# PS_cubesat_baterias.net
KiCad netlist of a schematic drawn in EAGLE
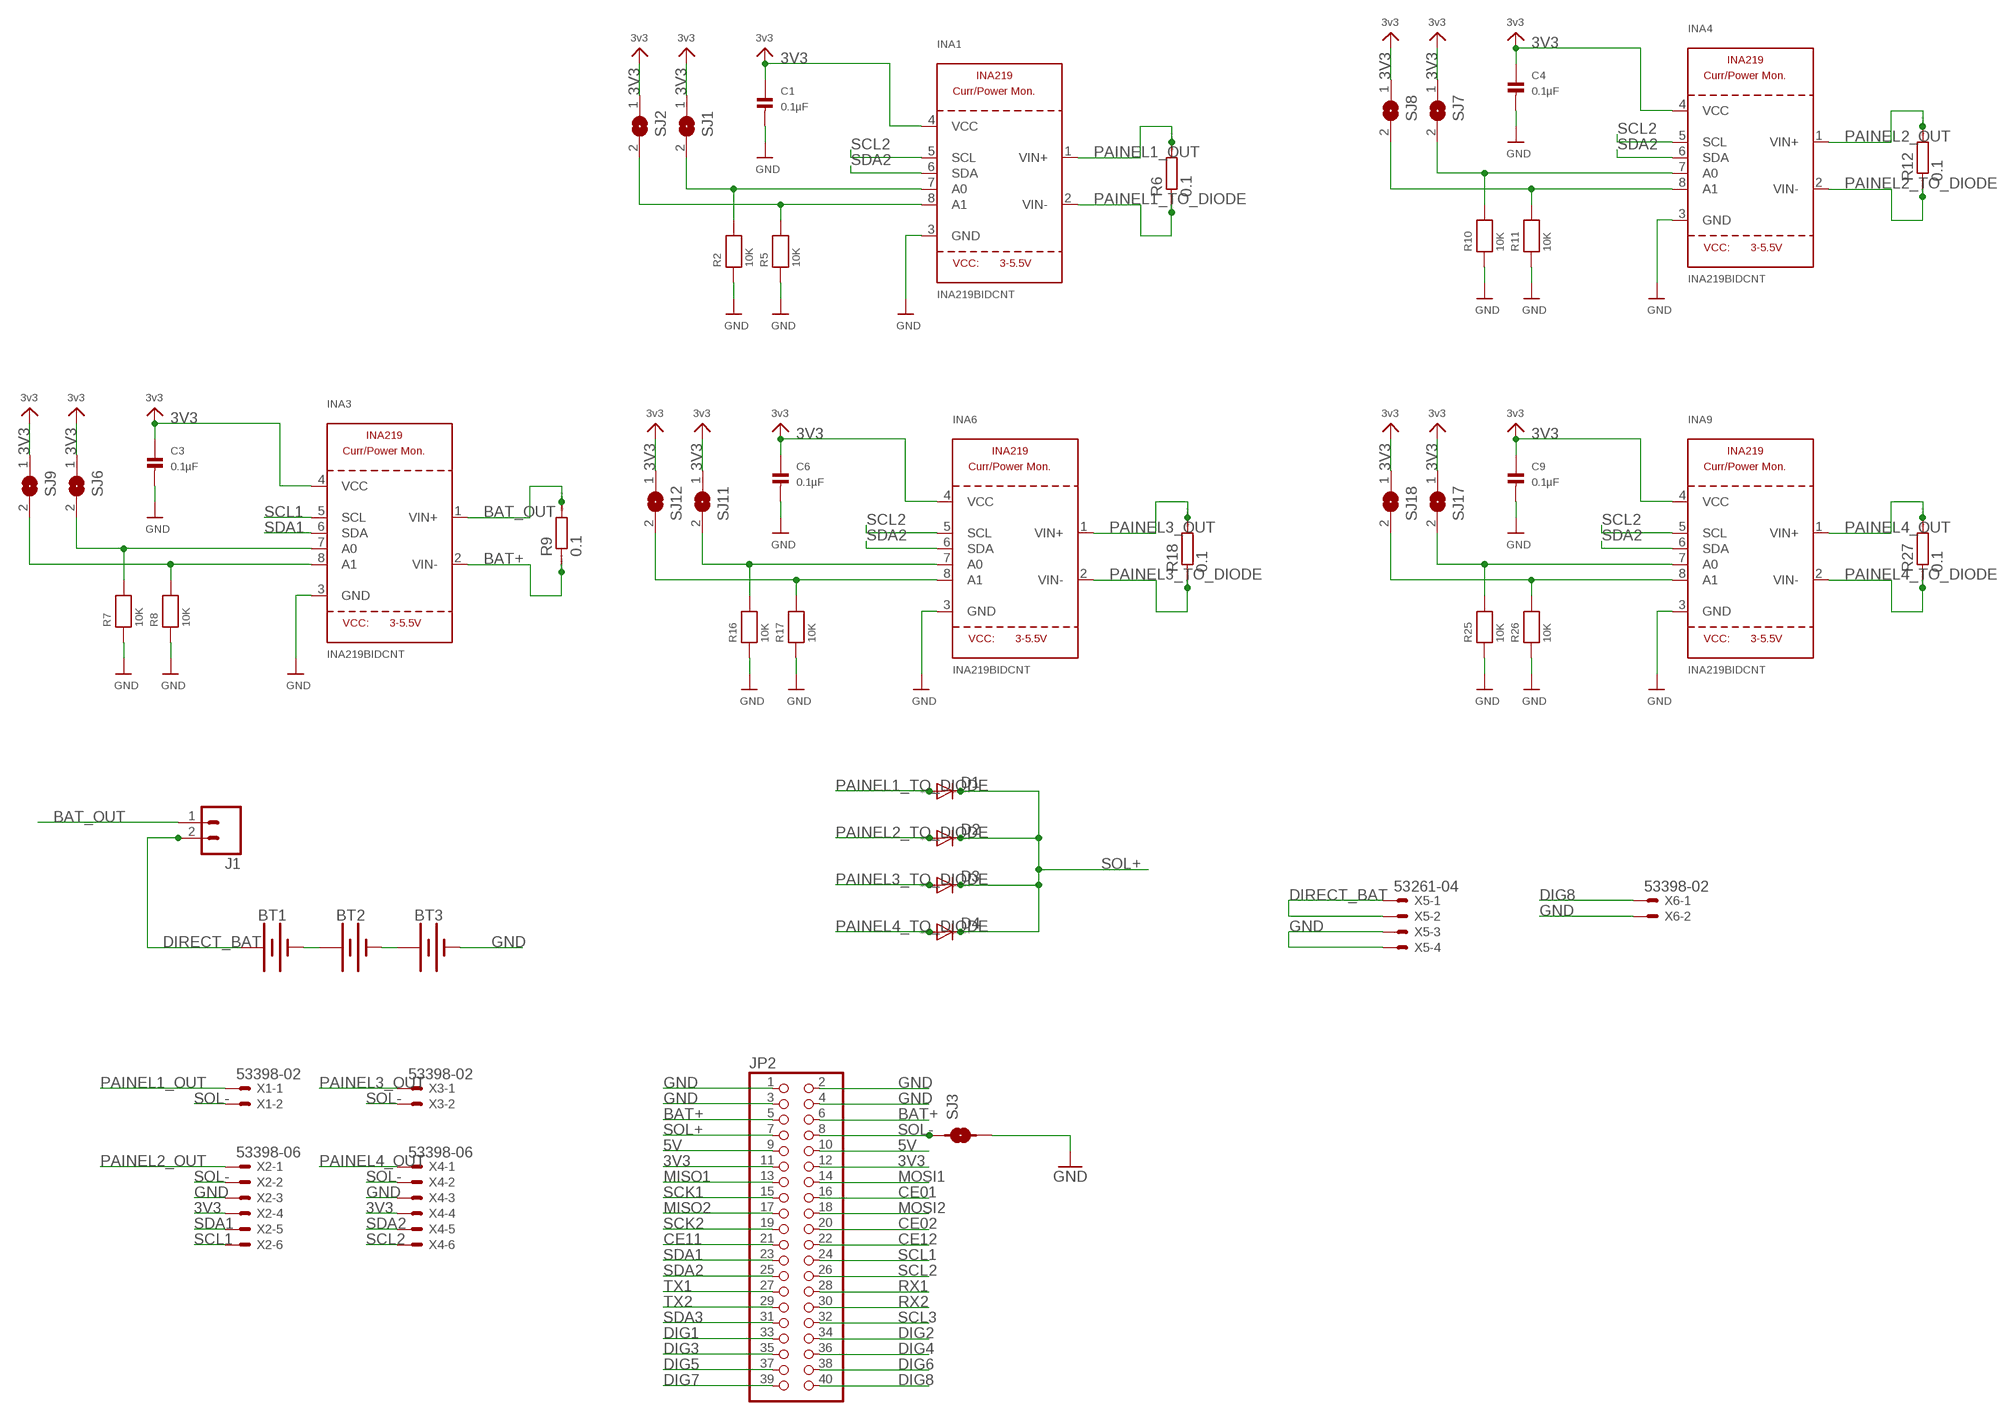
[diagram p0: schematic, sheet 1]

(export (version "E")
  (design (tool "Eeschema 10.0.6"))
  (components
    (comp (ref "BT1")
      (value "BATTERY-18650")
      (footprint "eagle-import:BATTERY_18650-HOLDER")
      (libsource (lib "eagle-import") (part "BATTERY-18650"))
    )
    (comp (ref "BT2")
      (value "BATTERY-18650")
      (footprint "eagle-import:BATTERY_18650-HOLDER")
      (libsource (lib "eagle-import") (part "BATTERY-18650"))
    )
    (comp (ref "BT3")
      (value "BATTERY-18650")
      (footprint "eagle-import:BATTERY_18650-HOLDER")
      (libsource (lib "eagle-import") (part "BATTERY-18650"))
    )
    (comp (ref "C1")
      (value "0.1µF")
      (footprint "eagle-import:1206")
      (libsource (lib "eagle-import") (part "CAP_CERAMIC1206"))
    )
    (comp (ref "C3")
      (value "0.1µF")
      (footprint "eagle-import:1206")
      (libsource (lib "eagle-import") (part "CAP_CERAMIC1206"))
    )
    (comp (ref "C4")
      (value "0.1µF")
      (footprint "eagle-import:1206")
      (libsource (lib "eagle-import") (part "CAP_CERAMIC1206"))
    )
    (comp (ref "C6")
      (value "0.1µF")
      (footprint "eagle-import:1206")
      (libsource (lib "eagle-import") (part "CAP_CERAMIC1206"))
    )
    (comp (ref "C9")
      (value "0.1µF")
      (footprint "eagle-import:1206")
      (libsource (lib "eagle-import") (part "CAP_CERAMIC1206"))
    )
    (comp (ref "D1")
      (value "DIODE-DO-214AC")
      (footprint "eagle-import:DO-214AC")
      (libsource (lib "eagle-import") (part "DIODE-DO-214AC"))
    )
    (comp (ref "D2")
      (value "DIODE-DO-214AC")
      (footprint "eagle-import:DO-214AC")
      (libsource (lib "eagle-import") (part "DIODE-DO-214AC"))
    )
    (comp (ref "D3")
      (value "DIODE-DO-214AC")
      (footprint "eagle-import:DO-214AC")
      (libsource (lib "eagle-import") (part "DIODE-DO-214AC"))
    )
    (comp (ref "D4")
      (value "DIODE-DO-214AC")
      (footprint "eagle-import:DO-214AC")
      (libsource (lib "eagle-import") (part "DIODE-DO-214AC"))
    )
    (comp (ref "INA1")
      (value "INA219BIDCNT")
      (footprint "eagle-import:SOT23-8")
      (libsource (lib "eagle-import") (part "INA219"))
    )
    (comp (ref "INA3")
      (value "INA219BIDCNT")
      (footprint "eagle-import:SOT23-8")
      (libsource (lib "eagle-import") (part "INA219"))
    )
    (comp (ref "INA4")
      (value "INA219BIDCNT")
      (footprint "eagle-import:SOT23-8")
      (libsource (lib "eagle-import") (part "INA219"))
    )
    (comp (ref "INA6")
      (value "INA219BIDCNT")
      (footprint "eagle-import:SOT23-8")
      (libsource (lib "eagle-import") (part "INA219"))
    )
    (comp (ref "INA9")
      (value "INA219BIDCNT")
      (footprint "eagle-import:SOT23-8")
      (libsource (lib "eagle-import") (part "INA219"))
    )
    (comp (ref "J1")
      (value "M02JST-PTH-VERT")
      (footprint "eagle-import:JST-2-PTH-VERT")
      (libsource (lib "eagle-import") (part "M02JST-PTH-VERT"))
    )
    (comp (ref "JP2")
      (value "PINHD-2X20")
      (footprint "eagle-import:2X20")
      (libsource (lib "eagle-import") (part "PINHD-2X20"))
    )
    (comp (ref "R2")
      (value "10K")
      (footprint "eagle-import:1206")
      (libsource (lib "eagle-import") (part "RESISTOR1206"))
    )
    (comp (ref "R5")
      (value "10K")
      (footprint "eagle-import:1206")
      (libsource (lib "eagle-import") (part "RESISTOR1206"))
    )
    (comp (ref "R6")
      (value "0.1")
      (footprint "eagle-import:R2512")
      (libsource (lib "eagle-import") (part "RR2512"))
    )
    (comp (ref "R7")
      (value "10K")
      (footprint "eagle-import:1206")
      (libsource (lib "eagle-import") (part "RESISTOR1206"))
    )
    (comp (ref "R8")
      (value "10K")
      (footprint "eagle-import:1206")
      (libsource (lib "eagle-import") (part "RESISTOR1206"))
    )
    (comp (ref "R9")
      (value "0.1")
      (footprint "eagle-import:R2512")
      (libsource (lib "eagle-import") (part "RR2512"))
    )
    (comp (ref "R10")
      (value "10K")
      (footprint "eagle-import:1206")
      (libsource (lib "eagle-import") (part "RESISTOR1206"))
    )
    (comp (ref "R11")
      (value "10K")
      (footprint "eagle-import:1206")
      (libsource (lib "eagle-import") (part "RESISTOR1206"))
    )
    (comp (ref "R12")
      (value "0.1")
      (footprint "eagle-import:R2512")
      (libsource (lib "eagle-import") (part "RR2512"))
    )
    (comp (ref "R16")
      (value "10K")
      (footprint "eagle-import:1206")
      (libsource (lib "eagle-import") (part "RESISTOR1206"))
    )
    (comp (ref "R17")
      (value "10K")
      (footprint "eagle-import:1206")
      (libsource (lib "eagle-import") (part "RESISTOR1206"))
    )
    (comp (ref "R18")
      (value "0.1")
      (footprint "eagle-import:R2512")
      (libsource (lib "eagle-import") (part "RR2512"))
    )
    (comp (ref "R25")
      (value "10K")
      (footprint "eagle-import:1206")
      (libsource (lib "eagle-import") (part "RESISTOR1206"))
    )
    (comp (ref "R26")
      (value "10K")
      (footprint "eagle-import:1206")
      (libsource (lib "eagle-import") (part "RESISTOR1206"))
    )
    (comp (ref "R27")
      (value "0.1")
      (footprint "eagle-import:R2512")
      (libsource (lib "eagle-import") (part "RR2512"))
    )
    (comp (ref "SJ1")
      (value "SOLDERJUMPERREFLOW_NOPASTE")
      (footprint "eagle-import:SOLDERJUMPER_REFLOW_NOPASTE")
      (libsource (lib "eagle-import") (part "SOLDERJUMPERREFLOW_NOPASTE"))
    )
    (comp (ref "SJ2")
      (value "SOLDERJUMPERREFLOW_NOPASTE")
      (footprint "eagle-import:SOLDERJUMPER_REFLOW_NOPASTE")
      (libsource (lib "eagle-import") (part "SOLDERJUMPERREFLOW_NOPASTE"))
    )
    (comp (ref "SJ3")
      (value "SMD-JUMPER-2")
      (footprint "eagle-import:SMD-JUMPER-2")
      (libsource (lib "eagle-import") (part "SMD-JUMPER-2"))
    )
    (comp (ref "SJ6")
      (value "SOLDERJUMPERREFLOW_NOPASTE")
      (footprint "eagle-import:SOLDERJUMPER_REFLOW_NOPASTE")
      (libsource (lib "eagle-import") (part "SOLDERJUMPERREFLOW_NOPASTE"))
    )
    (comp (ref "SJ7")
      (value "SOLDERJUMPERREFLOW_NOPASTE")
      (footprint "eagle-import:SOLDERJUMPER_REFLOW_NOPASTE")
      (libsource (lib "eagle-import") (part "SOLDERJUMPERREFLOW_NOPASTE"))
    )
    (comp (ref "SJ8")
      (value "SOLDERJUMPERREFLOW_NOPASTE")
      (footprint "eagle-import:SOLDERJUMPER_REFLOW_NOPASTE")
      (libsource (lib "eagle-import") (part "SOLDERJUMPERREFLOW_NOPASTE"))
    )
    (comp (ref "SJ9")
      (value "SOLDERJUMPERREFLOW_NOPASTE")
      (footprint "eagle-import:SOLDERJUMPER_REFLOW_NOPASTE")
      (libsource (lib "eagle-import") (part "SOLDERJUMPERREFLOW_NOPASTE"))
    )
    (comp (ref "SJ11")
      (value "SOLDERJUMPERREFLOW_NOPASTE")
      (footprint "eagle-import:SOLDERJUMPER_REFLOW_NOPASTE")
      (libsource (lib "eagle-import") (part "SOLDERJUMPERREFLOW_NOPASTE"))
    )
    (comp (ref "SJ12")
      (value "SOLDERJUMPERREFLOW_NOPASTE")
      (footprint "eagle-import:SOLDERJUMPER_REFLOW_NOPASTE")
      (libsource (lib "eagle-import") (part "SOLDERJUMPERREFLOW_NOPASTE"))
    )
    (comp (ref "SJ17")
      (value "SOLDERJUMPERREFLOW_NOPASTE")
      (footprint "eagle-import:SOLDERJUMPER_REFLOW_NOPASTE")
      (libsource (lib "eagle-import") (part "SOLDERJUMPERREFLOW_NOPASTE"))
    )
    (comp (ref "SJ18")
      (value "SOLDERJUMPERREFLOW_NOPASTE")
      (footprint "eagle-import:SOLDERJUMPER_REFLOW_NOPASTE")
      (libsource (lib "eagle-import") (part "SOLDERJUMPERREFLOW_NOPASTE"))
    )
    (comp (ref "X1")
      (value "53398-02")
      (footprint "eagle-import:53398-02")
      (fields (field (name "MF") "MOLEX"))
      (libsource (lib "eagle-import") (part "53?-02398"))
    )
    (comp (ref "X2")
      (value "53398-06")
      (footprint "eagle-import:53398-06")
      (fields (field (name "MF") "MOLEX"))
      (libsource (lib "eagle-import") (part "53?-06398"))
    )
    (comp (ref "X3")
      (value "53398-02")
      (footprint "eagle-import:53398-02")
      (fields (field (name "MF") "MOLEX"))
      (libsource (lib "eagle-import") (part "53?-02398"))
    )
    (comp (ref "X4")
      (value "53398-06")
      (footprint "eagle-import:53398-06")
      (fields (field (name "MF") "MOLEX"))
      (libsource (lib "eagle-import") (part "53?-06398"))
    )
    (comp (ref "X5")
      (value "53261-04")
      (footprint "eagle-import:53261-04")
      (fields (field (name "MF") "MOLEX"))
      (libsource (lib "eagle-import") (part "53?-04261"))
    )
    (comp (ref "X6")
      (value "53398-02")
      (footprint "eagle-import:53398-02")
      (fields (field (name "MF") "MOLEX"))
      (libsource (lib "eagle-import") (part "53?-02398"))
    )
  )
  (nets
    (net (code "1") (name "/5V") (class "Default")
      (node (ref "JP2") (pin "10") (pinfunction "10_10") (pintype "passive"))
      (node (ref "JP2") (pin "9") (pinfunction "9_9") (pintype "passive"))
    )
    (net (code "2") (name "/BAT+") (class "Default")
      (node (ref "INA3") (pin "2") (pinfunction "VIN-_2") (pintype "bidirectional"))
      (node (ref "JP2") (pin "5") (pinfunction "5_5") (pintype "passive"))
      (node (ref "JP2") (pin "6") (pinfunction "6_6") (pintype "passive"))
      (node (ref "R9") (pin "1") (pinfunction "1_1") (pintype "passive"))
    )
    (net (code "3") (name "/BAT_OUT") (class "Default")
      (node (ref "INA3") (pin "1") (pinfunction "VIN+_1") (pintype "bidirectional"))
      (node (ref "J1") (pin "1") (pinfunction "1_1") (pintype "passive"))
      (node (ref "R9") (pin "2") (pinfunction "2_2") (pintype "passive"))
    )
    (net (code "4") (name "/CE01") (class "Default")
      (node (ref "JP2") (pin "16") (pinfunction "16_16") (pintype "passive"))
    )
    (net (code "5") (name "/CE02") (class "Default")
      (node (ref "JP2") (pin "20") (pinfunction "20_20") (pintype "passive"))
    )
    (net (code "6") (name "/CE11") (class "Default")
      (node (ref "JP2") (pin "21") (pinfunction "21_21") (pintype "passive"))
    )
    (net (code "7") (name "/CE12") (class "Default")
      (node (ref "JP2") (pin "22") (pinfunction "22_22") (pintype "passive"))
    )
    (net (code "8") (name "/DIG1") (class "Default")
      (node (ref "JP2") (pin "33") (pinfunction "33_33") (pintype "passive"))
    )
    (net (code "9") (name "/DIG2") (class "Default")
      (node (ref "JP2") (pin "34") (pinfunction "34_34") (pintype "passive"))
    )
    (net (code "10") (name "/DIG3") (class "Default")
      (node (ref "JP2") (pin "35") (pinfunction "35_35") (pintype "passive"))
    )
    (net (code "11") (name "/DIG4") (class "Default")
      (node (ref "JP2") (pin "36") (pinfunction "36_36") (pintype "passive"))
    )
    (net (code "12") (name "/DIG5") (class "Default")
      (node (ref "JP2") (pin "37") (pinfunction "37_37") (pintype "passive"))
    )
    (net (code "13") (name "/DIG6") (class "Default")
      (node (ref "JP2") (pin "38") (pinfunction "38_38") (pintype "passive"))
    )
    (net (code "14") (name "/DIG7") (class "Default")
      (node (ref "JP2") (pin "39") (pinfunction "39_39") (pintype "passive"))
    )
    (net (code "15") (name "/DIG8") (class "Default")
      (node (ref "JP2") (pin "40") (pinfunction "40_40") (pintype "passive"))
      (node (ref "X6") (pin "1") (pinfunction "S_1") (pintype "passive"))
    )
    (net (code "16") (name "/DIRECT_BAT") (class "Default")
      (node (ref "BT1") (pin "PWR@1") (pinfunction "+_PWR@1") (pintype "power_in"))
      (node (ref "J1") (pin "2") (pinfunction "2_2") (pintype "passive"))
      (node (ref "X5") (pin "1") (pinfunction "S_1") (pintype "passive"))
      (node (ref "X5") (pin "2") (pinfunction "S_2") (pintype "passive"))
    )
    (net (code "17") (name "/MISO1") (class "Default")
      (node (ref "JP2") (pin "13") (pinfunction "13_13") (pintype "passive"))
    )
    (net (code "18") (name "/MISO2") (class "Default")
      (node (ref "JP2") (pin "17") (pinfunction "17_17") (pintype "passive"))
    )
    (net (code "19") (name "/MOSI1") (class "Default")
      (node (ref "JP2") (pin "14") (pinfunction "14_14") (pintype "passive"))
    )
    (net (code "20") (name "/MOSI2") (class "Default")
      (node (ref "JP2") (pin "18") (pinfunction "18_18") (pintype "passive"))
    )
    (net (code "21") (name "/PAINEL1_OUT") (class "Default")
      (node (ref "INA1") (pin "1") (pinfunction "VIN+_1") (pintype "bidirectional"))
      (node (ref "R6") (pin "2") (pinfunction "2_2") (pintype "passive"))
      (node (ref "X1") (pin "1") (pinfunction "S_1") (pintype "passive"))
    )
    (net (code "22") (name "/PAINEL1_TO_DIODE") (class "Default")
      (node (ref "D1") (pin "A") (pinfunction "A_A") (pintype "passive"))
      (node (ref "INA1") (pin "2") (pinfunction "VIN-_2") (pintype "bidirectional"))
      (node (ref "R6") (pin "1") (pinfunction "1_1") (pintype "passive"))
    )
    (net (code "23") (name "/PAINEL2_OUT") (class "Default")
      (node (ref "INA4") (pin "1") (pinfunction "VIN+_1") (pintype "bidirectional"))
      (node (ref "R12") (pin "2") (pinfunction "2_2") (pintype "passive"))
      (node (ref "X2") (pin "1") (pinfunction "S_1") (pintype "passive"))
    )
    (net (code "24") (name "/PAINEL2_TO_DIODE") (class "Default")
      (node (ref "D2") (pin "A") (pinfunction "A_A") (pintype "passive"))
      (node (ref "INA4") (pin "2") (pinfunction "VIN-_2") (pintype "bidirectional"))
      (node (ref "R12") (pin "1") (pinfunction "1_1") (pintype "passive"))
    )
    (net (code "25") (name "/PAINEL3_OUT") (class "Default")
      (node (ref "INA6") (pin "1") (pinfunction "VIN+_1") (pintype "bidirectional"))
      (node (ref "R18") (pin "2") (pinfunction "2_2") (pintype "passive"))
      (node (ref "X3") (pin "1") (pinfunction "S_1") (pintype "passive"))
    )
    (net (code "26") (name "/PAINEL3_TO_DIODE") (class "Default")
      (node (ref "D3") (pin "A") (pinfunction "A_A") (pintype "passive"))
      (node (ref "INA6") (pin "2") (pinfunction "VIN-_2") (pintype "bidirectional"))
      (node (ref "R18") (pin "1") (pinfunction "1_1") (pintype "passive"))
    )
    (net (code "27") (name "/PAINEL4_OUT") (class "Default")
      (node (ref "INA9") (pin "1") (pinfunction "VIN+_1") (pintype "bidirectional"))
      (node (ref "R27") (pin "2") (pinfunction "2_2") (pintype "passive"))
      (node (ref "X4") (pin "1") (pinfunction "S_1") (pintype "passive"))
    )
    (net (code "28") (name "/PAINEL4_TO_DIODE") (class "Default")
      (node (ref "D4") (pin "A") (pinfunction "A_A") (pintype "passive"))
      (node (ref "INA9") (pin "2") (pinfunction "VIN-_2") (pintype "bidirectional"))
      (node (ref "R27") (pin "1") (pinfunction "1_1") (pintype "passive"))
    )
    (net (code "29") (name "/RX1") (class "Default")
      (node (ref "JP2") (pin "28") (pinfunction "28_28") (pintype "passive"))
    )
    (net (code "30") (name "/RX2") (class "Default")
      (node (ref "JP2") (pin "30") (pinfunction "30_30") (pintype "passive"))
    )
    (net (code "31") (name "/SCK1") (class "Default")
      (node (ref "JP2") (pin "15") (pinfunction "15_15") (pintype "passive"))
    )
    (net (code "32") (name "/SCK2") (class "Default")
      (node (ref "JP2") (pin "19") (pinfunction "19_19") (pintype "passive"))
    )
    (net (code "33") (name "/SCL1") (class "Default")
      (node (ref "INA3") (pin "5") (pinfunction "SCL_5") (pintype "bidirectional"))
      (node (ref "JP2") (pin "24") (pinfunction "24_24") (pintype "passive"))
      (node (ref "X2") (pin "6") (pinfunction "S_6") (pintype "passive"))
    )
    (net (code "34") (name "/SCL2") (class "Default")
      (node (ref "INA1") (pin "5") (pinfunction "SCL_5") (pintype "bidirectional"))
      (node (ref "INA4") (pin "5") (pinfunction "SCL_5") (pintype "bidirectional"))
      (node (ref "INA6") (pin "5") (pinfunction "SCL_5") (pintype "bidirectional"))
      (node (ref "INA9") (pin "5") (pinfunction "SCL_5") (pintype "bidirectional"))
      (node (ref "JP2") (pin "26") (pinfunction "26_26") (pintype "passive"))
      (node (ref "X4") (pin "6") (pinfunction "S_6") (pintype "passive"))
    )
    (net (code "35") (name "/SCL3") (class "Default")
      (node (ref "JP2") (pin "32") (pinfunction "32_32") (pintype "passive"))
    )
    (net (code "36") (name "/SDA1") (class "Default")
      (node (ref "INA3") (pin "6") (pinfunction "SDA_6") (pintype "bidirectional"))
      (node (ref "JP2") (pin "23") (pinfunction "23_23") (pintype "passive"))
      (node (ref "X2") (pin "5") (pinfunction "S_5") (pintype "passive"))
    )
    (net (code "37") (name "/SDA2") (class "Default")
      (node (ref "INA1") (pin "6") (pinfunction "SDA_6") (pintype "bidirectional"))
      (node (ref "INA4") (pin "6") (pinfunction "SDA_6") (pintype "bidirectional"))
      (node (ref "INA6") (pin "6") (pinfunction "SDA_6") (pintype "bidirectional"))
      (node (ref "INA9") (pin "6") (pinfunction "SDA_6") (pintype "bidirectional"))
      (node (ref "JP2") (pin "25") (pinfunction "25_25") (pintype "passive"))
      (node (ref "X4") (pin "5") (pinfunction "S_5") (pintype "passive"))
    )
    (net (code "38") (name "/SDA3") (class "Default")
      (node (ref "JP2") (pin "31") (pinfunction "31_31") (pintype "passive"))
    )
    (net (code "39") (name "/SOL+") (class "Default")
      (node (ref "D1") (pin "C") (pinfunction "C_C") (pintype "passive"))
      (node (ref "D2") (pin "C") (pinfunction "C_C") (pintype "passive"))
      (node (ref "D3") (pin "C") (pinfunction "C_C") (pintype "passive"))
      (node (ref "D4") (pin "C") (pinfunction "C_C") (pintype "passive"))
      (node (ref "JP2") (pin "7") (pinfunction "7_7") (pintype "passive"))
    )
    (net (code "40") (name "/SOL-") (class "Default")
      (node (ref "JP2") (pin "8") (pinfunction "8_8") (pintype "passive"))
      (node (ref "SJ3") (pin "1") (pinfunction "1_1") (pintype "passive"))
      (node (ref "X1") (pin "2") (pinfunction "S_2") (pintype "passive"))
      (node (ref "X2") (pin "2") (pinfunction "S_2") (pintype "passive"))
      (node (ref "X3") (pin "2") (pinfunction "S_2") (pintype "passive"))
      (node (ref "X4") (pin "2") (pinfunction "S_2") (pintype "passive"))
    )
    (net (code "41") (name "/TX1") (class "Default")
      (node (ref "JP2") (pin "27") (pinfunction "27_27") (pintype "passive"))
    )
    (net (code "42") (name "/TX2") (class "Default")
      (node (ref "JP2") (pin "29") (pinfunction "29_29") (pintype "passive"))
    )
    (net (code "43") (name "3v3") (class "Default")
      (node (ref "C1") (pin "1") (pinfunction "P$1_1") (pintype "passive"))
      (node (ref "C3") (pin "1") (pinfunction "P$1_1") (pintype "passive"))
      (node (ref "C4") (pin "1") (pinfunction "P$1_1") (pintype "passive"))
      (node (ref "C6") (pin "1") (pinfunction "P$1_1") (pintype "passive"))
      (node (ref "C9") (pin "1") (pinfunction "P$1_1") (pintype "passive"))
      (node (ref "INA1") (pin "4") (pinfunction "VCC_4") (pintype "bidirectional"))
      (node (ref "INA3") (pin "4") (pinfunction "VCC_4") (pintype "bidirectional"))
      (node (ref "INA4") (pin "4") (pinfunction "VCC_4") (pintype "bidirectional"))
      (node (ref "INA6") (pin "4") (pinfunction "VCC_4") (pintype "bidirectional"))
      (node (ref "INA9") (pin "4") (pinfunction "VCC_4") (pintype "bidirectional"))
      (node (ref "JP2") (pin "11") (pinfunction "11_11") (pintype "passive"))
      (node (ref "JP2") (pin "12") (pinfunction "12_12") (pintype "passive"))
      (node (ref "SJ1") (pin "1") (pinfunction "1_1") (pintype "passive"))
      (node (ref "SJ11") (pin "1") (pinfunction "1_1") (pintype "passive"))
      (node (ref "SJ12") (pin "1") (pinfunction "1_1") (pintype "passive"))
      (node (ref "SJ17") (pin "1") (pinfunction "1_1") (pintype "passive"))
      (node (ref "SJ18") (pin "1") (pinfunction "1_1") (pintype "passive"))
      (node (ref "SJ2") (pin "1") (pinfunction "1_1") (pintype "passive"))
      (node (ref "SJ6") (pin "1") (pinfunction "1_1") (pintype "passive"))
      (node (ref "SJ7") (pin "1") (pinfunction "1_1") (pintype "passive"))
      (node (ref "SJ8") (pin "1") (pinfunction "1_1") (pintype "passive"))
      (node (ref "SJ9") (pin "1") (pinfunction "1_1") (pintype "passive"))
      (node (ref "X2") (pin "4") (pinfunction "S_4") (pintype "passive"))
      (node (ref "X4") (pin "4") (pinfunction "S_4") (pintype "passive"))
    )
    (net (code "44") (name "GND") (class "Default")
      (node (ref "BT3") (pin "GND@1") (pinfunction "-_GND@1") (pintype "power_in"))
      (node (ref "C1") (pin "2") (pinfunction "P$2_2") (pintype "passive"))
      (node (ref "C3") (pin "2") (pinfunction "P$2_2") (pintype "passive"))
      (node (ref "C4") (pin "2") (pinfunction "P$2_2") (pintype "passive"))
      (node (ref "C6") (pin "2") (pinfunction "P$2_2") (pintype "passive"))
      (node (ref "C9") (pin "2") (pinfunction "P$2_2") (pintype "passive"))
      (node (ref "INA1") (pin "3") (pinfunction "GND_3") (pintype "bidirectional"))
      (node (ref "INA3") (pin "3") (pinfunction "GND_3") (pintype "bidirectional"))
      (node (ref "INA4") (pin "3") (pinfunction "GND_3") (pintype "bidirectional"))
      (node (ref "INA6") (pin "3") (pinfunction "GND_3") (pintype "bidirectional"))
      (node (ref "INA9") (pin "3") (pinfunction "GND_3") (pintype "bidirectional"))
      (node (ref "JP2") (pin "1") (pinfunction "1_1") (pintype "passive"))
      (node (ref "JP2") (pin "2") (pinfunction "2_2") (pintype "passive"))
      (node (ref "JP2") (pin "3") (pinfunction "3_3") (pintype "passive"))
      (node (ref "JP2") (pin "4") (pinfunction "4_4") (pintype "passive"))
      (node (ref "R10") (pin "1") (pinfunction "1_1") (pintype "passive"))
      (node (ref "R11") (pin "1") (pinfunction "1_1") (pintype "passive"))
      (node (ref "R16") (pin "1") (pinfunction "1_1") (pintype "passive"))
      (node (ref "R17") (pin "1") (pinfunction "1_1") (pintype "passive"))
      (node (ref "R2") (pin "1") (pinfunction "1_1") (pintype "passive"))
      (node (ref "R25") (pin "1") (pinfunction "1_1") (pintype "passive"))
      (node (ref "R26") (pin "1") (pinfunction "1_1") (pintype "passive"))
      (node (ref "R5") (pin "1") (pinfunction "1_1") (pintype "passive"))
      (node (ref "R7") (pin "1") (pinfunction "1_1") (pintype "passive"))
      (node (ref "R8") (pin "1") (pinfunction "1_1") (pintype "passive"))
      (node (ref "SJ3") (pin "2") (pinfunction "2_2") (pintype "passive"))
      (node (ref "X2") (pin "3") (pinfunction "S_3") (pintype "passive"))
      (node (ref "X4") (pin "3") (pinfunction "S_3") (pintype "passive"))
      (node (ref "X5") (pin "3") (pinfunction "S_3") (pintype "passive"))
      (node (ref "X5") (pin "4") (pinfunction "S_4") (pintype "passive"))
      (node (ref "X6") (pin "2") (pinfunction "S_2") (pintype "passive"))
    )
    (net (code "45") (name "Net-(BT1--)") (class "Default")
      (node (ref "BT1") (pin "GND@1") (pinfunction "-_GND@1") (pintype "power_in"))
      (node (ref "BT2") (pin "PWR@1") (pinfunction "+_PWR@1") (pintype "power_in"))
    )
    (net (code "46") (name "Net-(BT2--)") (class "Default")
      (node (ref "BT2") (pin "GND@1") (pinfunction "-_GND@1") (pintype "power_in"))
      (node (ref "BT3") (pin "PWR@1") (pinfunction "+_PWR@1") (pintype "power_in"))
    )
    (net (code "47") (name "Net-(INA1-A0)") (class "Default")
      (node (ref "INA1") (pin "7") (pinfunction "A0_7") (pintype "bidirectional"))
      (node (ref "R2") (pin "2") (pinfunction "2_2") (pintype "passive"))
      (node (ref "SJ1") (pin "2") (pinfunction "2_2") (pintype "passive"))
    )
    (net (code "48") (name "Net-(INA1-A1)") (class "Default")
      (node (ref "INA1") (pin "8") (pinfunction "A1_8") (pintype "bidirectional"))
      (node (ref "R5") (pin "2") (pinfunction "2_2") (pintype "passive"))
      (node (ref "SJ2") (pin "2") (pinfunction "2_2") (pintype "passive"))
    )
    (net (code "49") (name "Net-(INA3-A0)") (class "Default")
      (node (ref "INA3") (pin "7") (pinfunction "A0_7") (pintype "bidirectional"))
      (node (ref "R7") (pin "2") (pinfunction "2_2") (pintype "passive"))
      (node (ref "SJ6") (pin "2") (pinfunction "2_2") (pintype "passive"))
    )
    (net (code "50") (name "Net-(INA3-A1)") (class "Default")
      (node (ref "INA3") (pin "8") (pinfunction "A1_8") (pintype "bidirectional"))
      (node (ref "R8") (pin "2") (pinfunction "2_2") (pintype "passive"))
      (node (ref "SJ9") (pin "2") (pinfunction "2_2") (pintype "passive"))
    )
    (net (code "51") (name "Net-(INA4-A0)") (class "Default")
      (node (ref "INA4") (pin "7") (pinfunction "A0_7") (pintype "bidirectional"))
      (node (ref "R10") (pin "2") (pinfunction "2_2") (pintype "passive"))
      (node (ref "SJ7") (pin "2") (pinfunction "2_2") (pintype "passive"))
    )
    (net (code "52") (name "Net-(INA4-A1)") (class "Default")
      (node (ref "INA4") (pin "8") (pinfunction "A1_8") (pintype "bidirectional"))
      (node (ref "R11") (pin "2") (pinfunction "2_2") (pintype "passive"))
      (node (ref "SJ8") (pin "2") (pinfunction "2_2") (pintype "passive"))
    )
    (net (code "53") (name "Net-(INA6-A0)") (class "Default")
      (node (ref "INA6") (pin "7") (pinfunction "A0_7") (pintype "bidirectional"))
      (node (ref "R16") (pin "2") (pinfunction "2_2") (pintype "passive"))
      (node (ref "SJ11") (pin "2") (pinfunction "2_2") (pintype "passive"))
    )
    (net (code "54") (name "Net-(INA6-A1)") (class "Default")
      (node (ref "INA6") (pin "8") (pinfunction "A1_8") (pintype "bidirectional"))
      (node (ref "R17") (pin "2") (pinfunction "2_2") (pintype "passive"))
      (node (ref "SJ12") (pin "2") (pinfunction "2_2") (pintype "passive"))
    )
    (net (code "55") (name "Net-(INA9-A0)") (class "Default")
      (node (ref "INA9") (pin "7") (pinfunction "A0_7") (pintype "bidirectional"))
      (node (ref "R25") (pin "2") (pinfunction "2_2") (pintype "passive"))
      (node (ref "SJ17") (pin "2") (pinfunction "2_2") (pintype "passive"))
    )
    (net (code "56") (name "Net-(INA9-A1)") (class "Default")
      (node (ref "INA9") (pin "8") (pinfunction "A1_8") (pintype "bidirectional"))
      (node (ref "R26") (pin "2") (pinfunction "2_2") (pintype "passive"))
      (node (ref "SJ18") (pin "2") (pinfunction "2_2") (pintype "passive"))
    )
  )
)
